# Multiplex.net
KiCad netlist of a schematic drawn in EAGLE
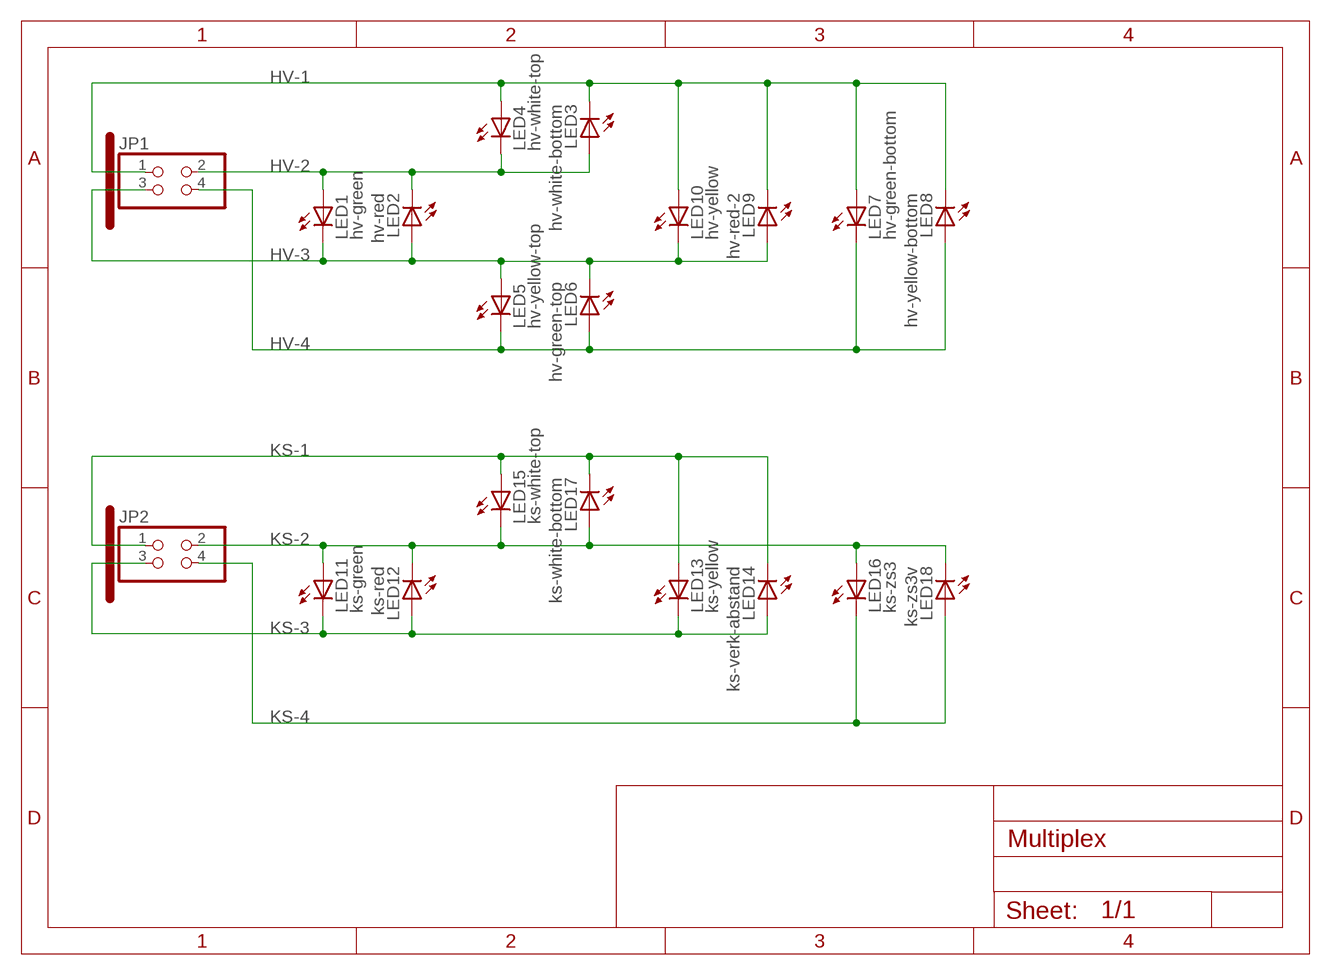
[diagram p0: schematic, sheet 1]

(export (version "E")
  (design (tool "Eeschema 10.0.6"))
  (components
    (comp (ref "JP1")
      (value "PINHD-2X2")
      (footprint "eagle-import:2X02")
      (libsource (lib "eagle-import") (part "PINHD-2X2"))
    )
    (comp (ref "JP2")
      (value "PINHD-2X2")
      (footprint "eagle-import:2X02")
      (libsource (lib "eagle-import") (part "PINHD-2X2"))
    )
    (comp (ref "LED1")
      (value "hv-green")
      (footprint "eagle-import:LED3MM")
      (libsource (lib "eagle-import") (part "LED3MM"))
    )
    (comp (ref "LED2")
      (value "hv-red")
      (footprint "eagle-import:LED3MM")
      (libsource (lib "eagle-import") (part "LED3MM"))
    )
    (comp (ref "LED3")
      (value "hv-white-bottom")
      (footprint "eagle-import:LED3MM")
      (libsource (lib "eagle-import") (part "LED3MM"))
    )
    (comp (ref "LED4")
      (value "hv-white-top")
      (footprint "eagle-import:LED3MM")
      (libsource (lib "eagle-import") (part "LED3MM"))
    )
    (comp (ref "LED5")
      (value "hv-yellow-top")
      (footprint "eagle-import:LED3MM")
      (libsource (lib "eagle-import") (part "LED3MM"))
    )
    (comp (ref "LED6")
      (value "hv-green-top")
      (footprint "eagle-import:LED3MM")
      (libsource (lib "eagle-import") (part "LED3MM"))
    )
    (comp (ref "LED7")
      (value "hv-green-bottom")
      (footprint "eagle-import:LED3MM")
      (libsource (lib "eagle-import") (part "LED3MM"))
    )
    (comp (ref "LED8")
      (value "hv-yellow-bottom")
      (footprint "eagle-import:LED3MM")
      (libsource (lib "eagle-import") (part "LED3MM"))
    )
    (comp (ref "LED9")
      (value "hv-red-2")
      (footprint "eagle-import:LED3MM")
      (libsource (lib "eagle-import") (part "LED3MM"))
    )
    (comp (ref "LED10")
      (value "hv-yellow")
      (footprint "eagle-import:LED3MM")
      (libsource (lib "eagle-import") (part "LED3MM"))
    )
    (comp (ref "LED11")
      (value "ks-green")
      (footprint "eagle-import:LED3MM")
      (libsource (lib "eagle-import") (part "LED3MM"))
    )
    (comp (ref "LED12")
      (value "ks-red")
      (footprint "eagle-import:LED3MM")
      (libsource (lib "eagle-import") (part "LED3MM"))
    )
    (comp (ref "LED13")
      (value "ks-yellow")
      (footprint "eagle-import:LED3MM")
      (libsource (lib "eagle-import") (part "LED3MM"))
    )
    (comp (ref "LED14")
      (value "ks-verk-abstand")
      (footprint "eagle-import:LED3MM")
      (libsource (lib "eagle-import") (part "LED3MM"))
    )
    (comp (ref "LED15")
      (value "ks-white-top")
      (footprint "eagle-import:LED3MM")
      (libsource (lib "eagle-import") (part "LED3MM"))
    )
    (comp (ref "LED16")
      (value "ks-zs3")
      (footprint "eagle-import:LED3MM")
      (libsource (lib "eagle-import") (part "LED3MM"))
    )
    (comp (ref "LED17")
      (value "ks-white-bottom")
      (footprint "eagle-import:LED3MM")
      (libsource (lib "eagle-import") (part "LED3MM"))
    )
    (comp (ref "LED18")
      (value "ks-zs3v")
      (footprint "eagle-import:LED3MM")
      (libsource (lib "eagle-import") (part "LED3MM"))
    )
  )
  (nets
    (net (code "1") (name "/HV-1") (class "Default")
      (node (ref "JP1") (pin "1") (pinfunction "1_1") (pintype "passive"))
      (node (ref "LED10") (pin "A") (pinfunction "A_A") (pintype "passive"))
      (node (ref "LED3") (pin "K") (pinfunction "C_K") (pintype "passive"))
      (node (ref "LED4") (pin "A") (pinfunction "A_A") (pintype "passive"))
      (node (ref "LED7") (pin "A") (pinfunction "A_A") (pintype "passive"))
      (node (ref "LED8") (pin "K") (pinfunction "C_K") (pintype "passive"))
      (node (ref "LED9") (pin "K") (pinfunction "C_K") (pintype "passive"))
    )
    (net (code "2") (name "/HV-2") (class "Default")
      (node (ref "JP1") (pin "2") (pinfunction "2_2") (pintype "passive"))
      (node (ref "LED1") (pin "A") (pinfunction "A_A") (pintype "passive"))
      (node (ref "LED2") (pin "K") (pinfunction "C_K") (pintype "passive"))
      (node (ref "LED3") (pin "A") (pinfunction "A_A") (pintype "passive"))
      (node (ref "LED4") (pin "K") (pinfunction "C_K") (pintype "passive"))
    )
    (net (code "3") (name "/HV-3") (class "Default")
      (node (ref "JP1") (pin "3") (pinfunction "3_3") (pintype "passive"))
      (node (ref "LED1") (pin "K") (pinfunction "C_K") (pintype "passive"))
      (node (ref "LED10") (pin "K") (pinfunction "C_K") (pintype "passive"))
      (node (ref "LED2") (pin "A") (pinfunction "A_A") (pintype "passive"))
      (node (ref "LED5") (pin "A") (pinfunction "A_A") (pintype "passive"))
      (node (ref "LED6") (pin "K") (pinfunction "C_K") (pintype "passive"))
      (node (ref "LED9") (pin "A") (pinfunction "A_A") (pintype "passive"))
    )
    (net (code "4") (name "/HV-4") (class "Default")
      (node (ref "JP1") (pin "4") (pinfunction "4_4") (pintype "passive"))
      (node (ref "LED5") (pin "K") (pinfunction "C_K") (pintype "passive"))
      (node (ref "LED6") (pin "A") (pinfunction "A_A") (pintype "passive"))
      (node (ref "LED7") (pin "K") (pinfunction "C_K") (pintype "passive"))
      (node (ref "LED8") (pin "A") (pinfunction "A_A") (pintype "passive"))
    )
    (net (code "5") (name "/KS-1") (class "Default")
      (node (ref "JP2") (pin "1") (pinfunction "1_1") (pintype "passive"))
      (node (ref "LED13") (pin "A") (pinfunction "A_A") (pintype "passive"))
      (node (ref "LED14") (pin "K") (pinfunction "C_K") (pintype "passive"))
      (node (ref "LED15") (pin "A") (pinfunction "A_A") (pintype "passive"))
      (node (ref "LED17") (pin "K") (pinfunction "C_K") (pintype "passive"))
    )
    (net (code "6") (name "/KS-2") (class "Default")
      (node (ref "JP2") (pin "2") (pinfunction "2_2") (pintype "passive"))
      (node (ref "LED11") (pin "A") (pinfunction "A_A") (pintype "passive"))
      (node (ref "LED12") (pin "K") (pinfunction "C_K") (pintype "passive"))
      (node (ref "LED15") (pin "K") (pinfunction "C_K") (pintype "passive"))
      (node (ref "LED16") (pin "A") (pinfunction "A_A") (pintype "passive"))
      (node (ref "LED17") (pin "A") (pinfunction "A_A") (pintype "passive"))
      (node (ref "LED18") (pin "K") (pinfunction "C_K") (pintype "passive"))
    )
    (net (code "7") (name "/KS-3") (class "Default")
      (node (ref "JP2") (pin "3") (pinfunction "3_3") (pintype "passive"))
      (node (ref "LED11") (pin "K") (pinfunction "C_K") (pintype "passive"))
      (node (ref "LED12") (pin "A") (pinfunction "A_A") (pintype "passive"))
      (node (ref "LED13") (pin "K") (pinfunction "C_K") (pintype "passive"))
      (node (ref "LED14") (pin "A") (pinfunction "A_A") (pintype "passive"))
    )
    (net (code "8") (name "/KS-4") (class "Default")
      (node (ref "JP2") (pin "4") (pinfunction "4_4") (pintype "passive"))
      (node (ref "LED16") (pin "K") (pinfunction "C_K") (pintype "passive"))
      (node (ref "LED18") (pin "A") (pinfunction "A_A") (pintype "passive"))
    )
  )
)
